# Main_Board_-_Double_v3.net
KiCad netlist of a schematic drawn in EAGLE
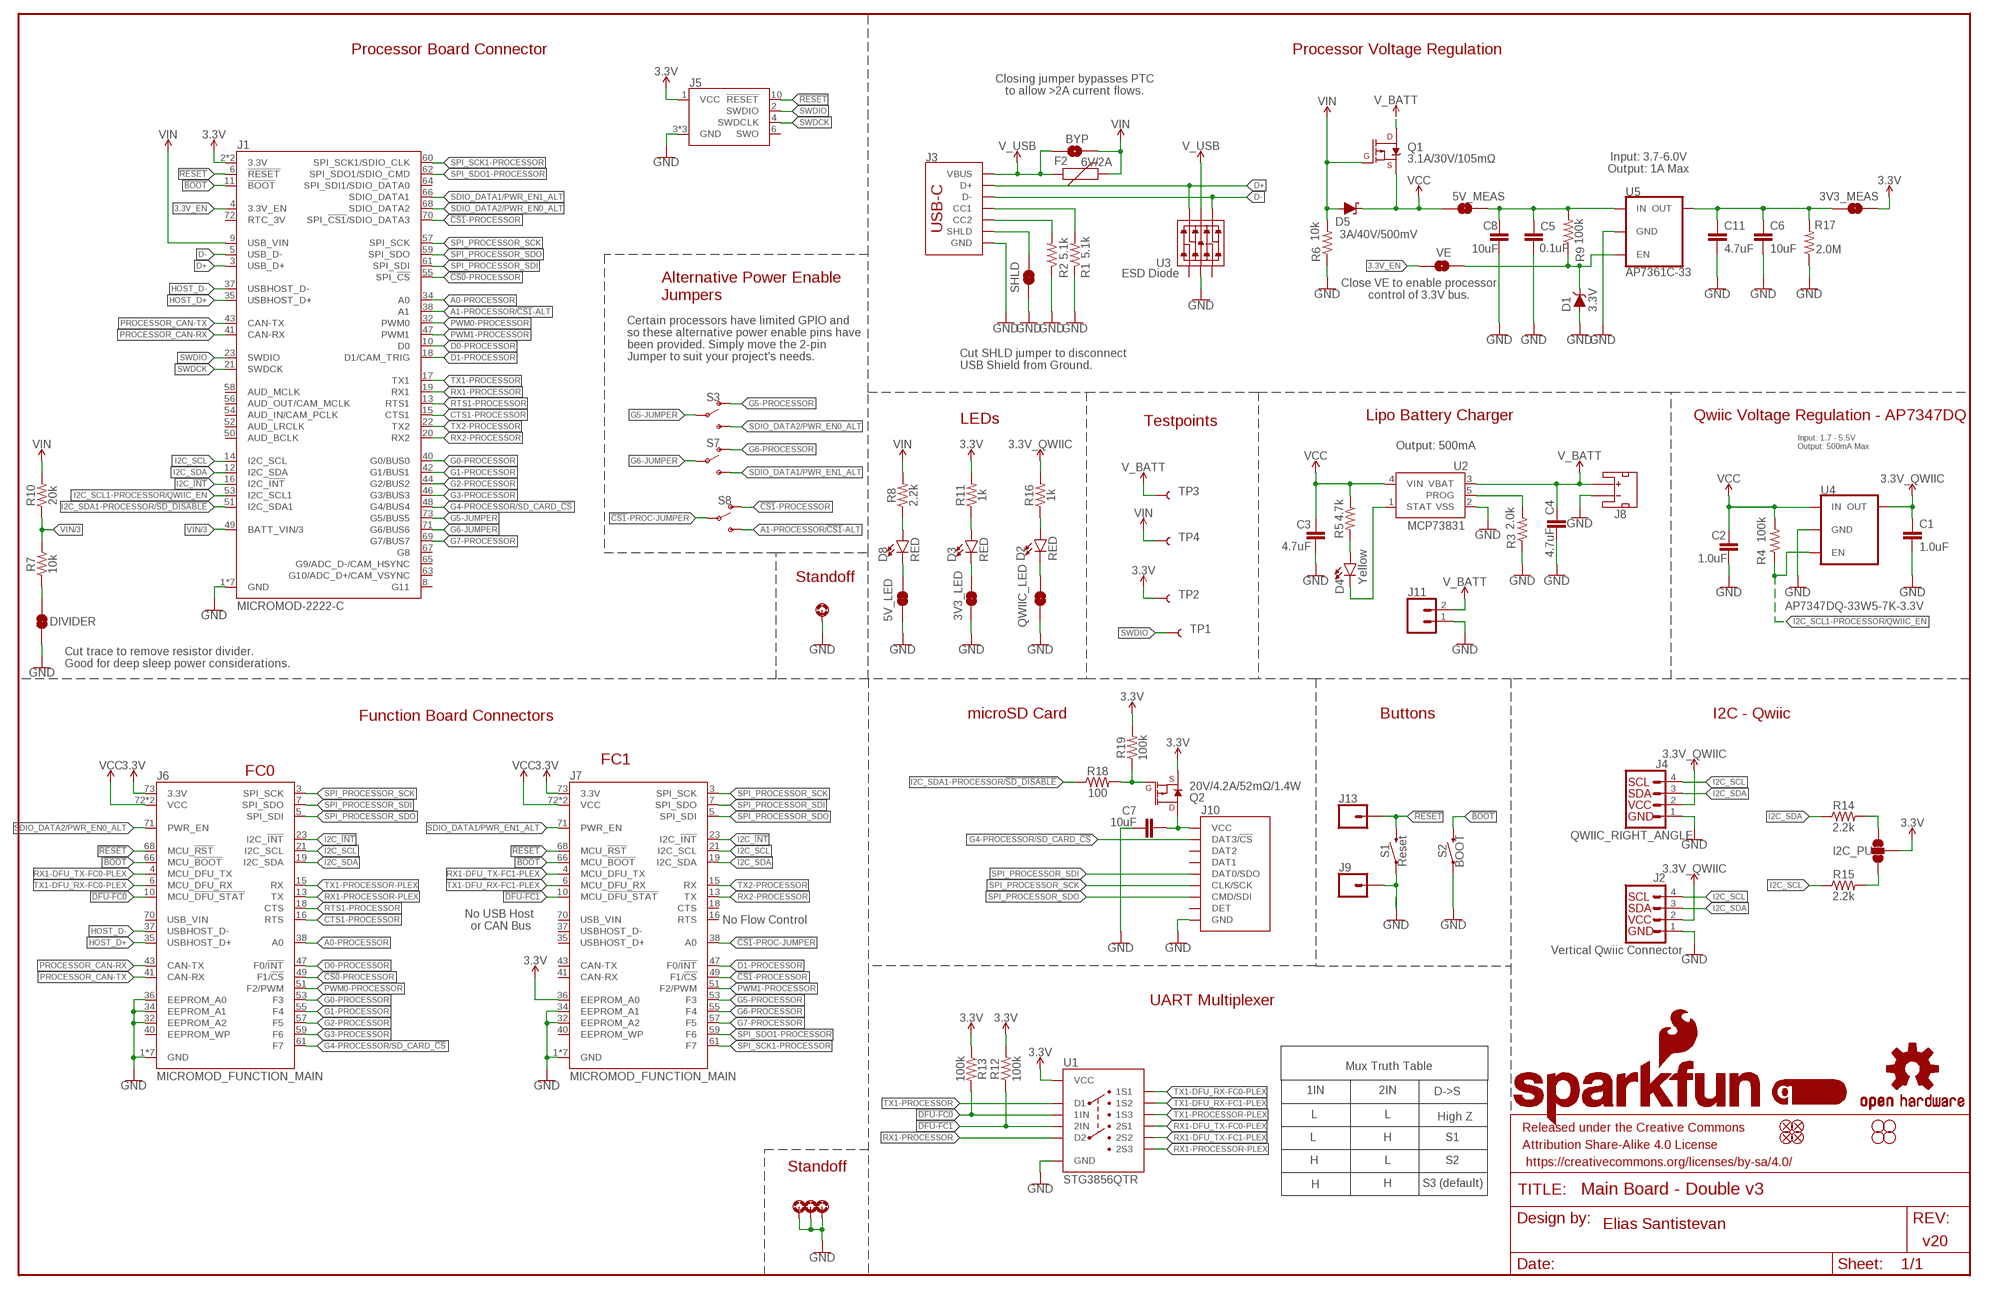
[diagram p0: schematic, sheet 1]

(export (version "E")
  (design (tool "Eeschema 10.0.6"))
  (components
    (comp (ref "3V3_LED")
      (value "JUMPER-SMT_2_NC_TRACE_SILK")
      (footprint "eagle-import:SMT-JUMPER_2_NC_TRACE_SILK")
      (libsource (lib "eagle-import") (part "JUMPER-SMT_2_NC_TRACE_SILK"))
    )
    (comp (ref "3V3_MEAS")
      (value "JUMPER-COMBO_2_NC_TRACE")
      (footprint "eagle-import:COMBO-JUMPER_2_NC_TRACE")
      (libsource (lib "eagle-import") (part "JUMPER-COMBO_2_NC_TRACE"))
    )
    (comp (ref "5V_LED")
      (value "JUMPER-SMT_2_NC_TRACE_SILK")
      (footprint "eagle-import:SMT-JUMPER_2_NC_TRACE_SILK")
      (libsource (lib "eagle-import") (part "JUMPER-SMT_2_NC_TRACE_SILK"))
    )
    (comp (ref "5V_MEAS")
      (value "JUMPER-COMBO_2_NC_TRACE")
      (footprint "eagle-import:COMBO-JUMPER_2_NC_TRACE")
      (libsource (lib "eagle-import") (part "JUMPER-COMBO_2_NC_TRACE"))
    )
    (comp (ref "BYP")
      (value "JUMPER-SMT_2_NO_SILK")
      (footprint "eagle-import:SMT-JUMPER_2_NO_SILK")
      (libsource (lib "eagle-import") (part "JUMPER-SMT_2_NO_SILK"))
    )
    (comp (ref "C1")
      (value "1.0uF")
      (footprint "eagle-import:0603")
      (libsource (lib "eagle-import") (part "1.0UF-0603-16V-10%"))
    )
    (comp (ref "C2")
      (value "1.0uF")
      (footprint "eagle-import:0603")
      (libsource (lib "eagle-import") (part "1.0UF-0603-16V-10%"))
    )
    (comp (ref "C3")
      (value "4.7uF")
      (footprint "eagle-import:0603")
      (libsource (lib "eagle-import") (part "4.7UF-0603-6.3V-(10%)"))
    )
    (comp (ref "C4")
      (value "4.7uF")
      (footprint "eagle-import:0603")
      (libsource (lib "eagle-import") (part "4.7UF-0603-35V-(20%)"))
    )
    (comp (ref "C5")
      (value "0.1uF")
      (footprint "eagle-import:0603")
      (libsource (lib "eagle-import") (part "0.1UF-0603-25V-(+80/-20%)"))
    )
    (comp (ref "C6")
      (value "10uF")
      (footprint "eagle-import:0805")
      (libsource (lib "eagle-import") (part "10UF-0805-10V-10%"))
    )
    (comp (ref "C7")
      (value "10uF")
      (footprint "eagle-import:0603")
      (libsource (lib "eagle-import") (part "10UF-0603-6.3V-20%"))
    )
    (comp (ref "C8")
      (value "10uF")
      (footprint "eagle-import:0805")
      (libsource (lib "eagle-import") (part "10UF-0805-10V-10%"))
    )
    (comp (ref "C11")
      (value "4.7uF")
      (footprint "eagle-import:0603")
      (libsource (lib "eagle-import") (part "4.7UF-0603-6.3V-(10%)"))
    )
    (comp (ref "D1")
      (value "3.3V")
      (footprint "eagle-import:SOD-323")
      (libsource (lib "eagle-import") (part "DIODE-ZENER-MM3Z3V3T1G"))
    )
    (comp (ref "D2")
      (value "RED")
      (footprint "eagle-import:LED-0603")
      (libsource (lib "eagle-import") (part "LED-RED0603"))
    )
    (comp (ref "D3")
      (value "RED")
      (footprint "eagle-import:LED-0603")
      (libsource (lib "eagle-import") (part "LED-RED0603"))
    )
    (comp (ref "D4")
      (value "Yellow")
      (footprint "eagle-import:LED-0603")
      (libsource (lib "eagle-import") (part "LED-YELLOW0603"))
    )
    (comp (ref "D5")
      (value "3A/40V/500mV")
      (footprint "eagle-import:SMA-DIODE")
      (libsource (lib "eagle-import") (part "DIODE-SCHOTTKY-B340A"))
    )
    (comp (ref "D8")
      (value "RED")
      (footprint "eagle-import:LED-0603")
      (libsource (lib "eagle-import") (part "LED-RED0603"))
    )
    (comp (ref "DIVIDER")
      (value "JUMPER-SMT_2_NC_TRACE_SILK")
      (footprint "eagle-import:SMT-JUMPER_2_NC_TRACE_SILK")
      (libsource (lib "eagle-import") (part "JUMPER-SMT_2_NC_TRACE_SILK"))
    )
    (comp (ref "F2")
      (value "6V/2A")
      (footprint "eagle-import:1210")
      (libsource (lib "eagle-import") (part "PPTC_6V2A"))
    )
    (comp (ref "FD1")
      (value "FIDUCIAL1X2")
      (footprint "eagle-import:FIDUCIAL-1X2")
      (libsource (lib "eagle-import") (part "FIDUCIAL1X2"))
    )
    (comp (ref "FD2")
      (value "FIDUCIAL1X2")
      (footprint "eagle-import:FIDUCIAL-1X2")
      (libsource (lib "eagle-import") (part "FIDUCIAL1X2"))
    )
    (comp (ref "FD3")
      (value "FIDUCIAL1X2")
      (footprint "eagle-import:FIDUCIAL-1X2")
      (libsource (lib "eagle-import") (part "FIDUCIAL1X2"))
    )
    (comp (ref "FD4")
      (value "FIDUCIAL1X2")
      (footprint "eagle-import:FIDUCIAL-1X2")
      (libsource (lib "eagle-import") (part "FIDUCIAL1X2"))
    )
    (comp (ref "FRAME1")
      (value "FRAME-LEDGER")
      (footprint "eagle-import:CREATIVE_COMMONS")
      (libsource (lib "eagle-import") (part "FRAME-LEDGER"))
    )
    (comp (ref "H2")
      (value "STAND-OFF-REFLOW-M2.5_2.5MM_TALL")
      (footprint "eagle-import:STAND-OFF-REFLOW-M2.5")
      (libsource (lib "eagle-import") (part "STAND-OFF-REFLOW-M2.5_2.5MM_TALL"))
    )
    (comp (ref "H3")
      (value "STAND-OFF-REFLOW-M2.5_2.5MM_TALL")
      (footprint "eagle-import:STAND-OFF-REFLOW-M2.5")
      (libsource (lib "eagle-import") (part "STAND-OFF-REFLOW-M2.5_2.5MM_TALL"))
    )
    (comp (ref "H4")
      (value "STAND-OFF-REFLOW-M2.5_2.5MM_TALL")
      (footprint "eagle-import:STAND-OFF-REFLOW-M2.5")
      (libsource (lib "eagle-import") (part "STAND-OFF-REFLOW-M2.5_2.5MM_TALL"))
    )
    (comp (ref "H8")
      (value "STAND-OFF-REFLOW-M2.5_2.5MM_TALL")
      (footprint "eagle-import:STAND-OFF-REFLOW-M2.5")
      (libsource (lib "eagle-import") (part "STAND-OFF-REFLOW-M2.5_2.5MM_TALL"))
    )
    (comp (ref "H14")
      (value "STAND-OFFTIGHT")
      (footprint "eagle-import:STAND-OFF-TIGHT")
      (libsource (lib "eagle-import") (part "STAND-OFFTIGHT"))
    )
    (comp (ref "H15")
      (value "STAND-OFFTIGHT")
      (footprint "eagle-import:STAND-OFF-TIGHT")
      (libsource (lib "eagle-import") (part "STAND-OFFTIGHT"))
    )
    (comp (ref "H16")
      (value "STAND-OFFTIGHT")
      (footprint "eagle-import:STAND-OFF-TIGHT")
      (libsource (lib "eagle-import") (part "STAND-OFFTIGHT"))
    )
    (comp (ref "H17")
      (value "STAND-OFFTIGHT")
      (footprint "eagle-import:STAND-OFF-TIGHT")
      (libsource (lib "eagle-import") (part "STAND-OFFTIGHT"))
    )
    (comp (ref "I2C_PU")
      (value "JUMPER-SMT_3_2-NC_TRACE_SILK")
      (footprint "eagle-import:SMT-JUMPER_3_2-NC_TRACE_SILK")
      (libsource (lib "eagle-import") (part "JUMPER-SMT_3_2-NC_TRACE_SILK"))
    )
    (comp (ref "J1")
      (value "MICROMOD-2222-C")
      (footprint "eagle-import:M.2-CONNECTOR-E")
      (libsource (lib "eagle-import") (part "MICROMOD-2222-C"))
    )
    (comp (ref "J2")
      (value "Vertical Qwiic Connector")
      (footprint "eagle-import:JST04_1MM_VERT")
      (libsource (lib "eagle-import") (part "QWIIC_CONNECTOR"))
    )
    (comp (ref "J3")
      (value "USB_C_2-LAYER_PADS")
      (footprint "eagle-import:USB-C-16P-2LAYER-PADS")
      (libsource (lib "eagle-import") (part "USB_C_2-LAYER_PADS"))
    )
    (comp (ref "J4")
      (value "QWIIC_RIGHT_ANGLE")
      (footprint "eagle-import:JST04_1MM_RA")
      (libsource (lib "eagle-import") (part "QWIIC_CONNECTORJS-1MM"))
    )
    (comp (ref "J5")
      (value "CORTEX_JTAG_DEBUG_MINIMUM_PTH")
      (footprint "eagle-import:2X5-PTH-1.27MM")
      (libsource (lib "eagle-import") (part "CORTEX_JTAG_DEBUG_MINIMUM_PTH"))
    )
    (comp (ref "J6")
      (value "MICROMOD_FUNCTION_MAIN")
      (footprint "eagle-import:M.2-CONNECTOR-E-FUNCTION-STANDARD")
      (libsource (lib "eagle-import") (part "MICROMOD_FUNCTION_MAIN"))
    )
    (comp (ref "J7")
      (value "MICROMOD_FUNCTION_MAIN")
      (footprint "eagle-import:M.2-CONNECTOR-E-FUNCTION-STANDARD")
      (libsource (lib "eagle-import") (part "MICROMOD_FUNCTION_MAIN"))
    )
    (comp (ref "J8")
      (value "JST_2MM_MALE")
      (footprint "eagle-import:JST-2-SMD")
      (libsource (lib "eagle-import") (part "JST_2MM_MALE"))
    )
    (comp (ref "J9")
      (value "CONN_01PTH_NO_SILK_YES_STOP")
      (footprint "eagle-import:1X01_NO_SILK")
      (libsource (lib "eagle-import") (part "CONN_01PTH_NO_SILK_YES_STOP"))
    )
    (comp (ref "J10")
      (value "MICRO-SD-PUSH-PUSH-EXT-PIN")
      (footprint "eagle-import:MICROSD-EXTERNALPIN")
      (libsource (lib "eagle-import") (part "MICRO-SD-PUSH-PUSH-EXT-PIN"))
    )
    (comp (ref "J11")
      (value "CONN_021X02_NO_SILK")
      (footprint "eagle-import:1X02_NO_SILK")
      (libsource (lib "eagle-import") (part "CONN_021X02_NO_SILK"))
    )
    (comp (ref "J13")
      (value "CONN_01PTH_NO_SILK_YES_STOP")
      (footprint "eagle-import:1X01_NO_SILK")
      (libsource (lib "eagle-import") (part "CONN_01PTH_NO_SILK_YES_STOP"))
    )
    (comp (ref "LOGO1")
      (value "QWIIC_LOGO_8MM")
      (footprint "eagle-import:QWIIC_8MM")
      (libsource (lib "eagle-import") (part "QWIIC_LOGO_8MM"))
    )
    (comp (ref "LOGO2")
      (value "SFE_LOGO_NAME_FLAME.3_INCH")
      (footprint "eagle-import:SFE_LOGO_NAME_FLAME_.3")
      (libsource (lib "eagle-import") (part "SFE_LOGO_NAME_FLAME.3_INCH"))
    )
    (comp (ref "LOGO3")
      (value "OSHW-LOGOL")
      (footprint "eagle-import:OSHW-LOGO-L")
      (libsource (lib "eagle-import") (part "OSHW-LOGOL"))
    )
    (comp (ref "Q1")
      (value "3.1A/30V/105mΩ")
      (footprint "eagle-import:SOT23-3")
      (libsource (lib "eagle-import") (part "MOSFET_PCH-DMG2307L"))
    )
    (comp (ref "Q2")
      (value "20V/4.2A/52mΩ/1.4W")
      (footprint "eagle-import:SOT23-3")
      (libsource (lib "eagle-import") (part "MOSFET_PCH-DMG2305UX-7"))
    )
    (comp (ref "QWIIC_LED")
      (value "JUMPER-SMT_2_NC_TRACE_SILK")
      (footprint "eagle-import:SMT-JUMPER_2_NC_TRACE_SILK")
      (libsource (lib "eagle-import") (part "JUMPER-SMT_2_NC_TRACE_SILK"))
    )
    (comp (ref "R1")
      (value "5.1k")
      (footprint "eagle-import:0603")
      (libsource (lib "eagle-import") (part "5.1KOHM5.1KOHM-0603-1/10W-1%"))
    )
    (comp (ref "R2")
      (value "5.1k")
      (footprint "eagle-import:0603")
      (libsource (lib "eagle-import") (part "5.1KOHM5.1KOHM-0603-1/10W-1%"))
    )
    (comp (ref "R3")
      (value "2.0k")
      (footprint "eagle-import:0603")
      (libsource (lib "eagle-import") (part "2.0KOHM-0603-1/10W-5%"))
    )
    (comp (ref "R4")
      (value "100k")
      (footprint "eagle-import:0603")
      (libsource (lib "eagle-import") (part "100KOHM-0603-1/10W-1%"))
    )
    (comp (ref "R5")
      (value "4.7k")
      (footprint "eagle-import:0603")
      (libsource (lib "eagle-import") (part "4.7KOHM-0603-1/10W-1%"))
    )
    (comp (ref "R6")
      (value "10k")
      (footprint "eagle-import:0603")
      (libsource (lib "eagle-import") (part "10KOHM-0603-1/10W-1%"))
    )
    (comp (ref "R7")
      (value "10k")
      (footprint "eagle-import:0603")
      (libsource (lib "eagle-import") (part "10KOHM-0603-1/10W-1%"))
    )
    (comp (ref "R8")
      (value "2.2k")
      (footprint "eagle-import:0603")
      (libsource (lib "eagle-import") (part "2.2KOHM-0603-1/10W-1%"))
    )
    (comp (ref "R9")
      (value "100k")
      (footprint "eagle-import:0603")
      (libsource (lib "eagle-import") (part "100KOHM-0603-1/10W-1%"))
    )
    (comp (ref "R10")
      (value "20k")
      (footprint "eagle-import:0603")
      (libsource (lib "eagle-import") (part "20KOHM-0603-1/10W-1%"))
    )
    (comp (ref "R11")
      (value "1k")
      (footprint "eagle-import:0603")
      (libsource (lib "eagle-import") (part "1KOHM-0603-1/10W-1%"))
    )
    (comp (ref "R12")
      (value "100k")
      (footprint "eagle-import:0603")
      (libsource (lib "eagle-import") (part "100KOHM-0603-1/10W-1%"))
    )
    (comp (ref "R13")
      (value "100k")
      (footprint "eagle-import:0603")
      (libsource (lib "eagle-import") (part "100KOHM-0603-1/10W-1%"))
    )
    (comp (ref "R14")
      (value "2.2k")
      (footprint "eagle-import:0603")
      (libsource (lib "eagle-import") (part "2.2KOHM-0603-1/10W-1%"))
    )
    (comp (ref "R15")
      (value "2.2k")
      (footprint "eagle-import:0603")
      (libsource (lib "eagle-import") (part "2.2KOHM-0603-1/10W-1%"))
    )
    (comp (ref "R16")
      (value "1k")
      (footprint "eagle-import:0603")
      (libsource (lib "eagle-import") (part "1KOHM-0603-1/10W-1%"))
    )
    (comp (ref "R17")
      (value "2.0M")
      (footprint "eagle-import:0603")
      (libsource (lib "eagle-import") (part "2MOHMS-0603-1/10W-1%"))
    )
    (comp (ref "R18")
      (value "100")
      (footprint "eagle-import:0603")
      (libsource (lib "eagle-import") (part "100OHM-0603-1/10W-1%"))
    )
    (comp (ref "R19")
      (value "100k")
      (footprint "eagle-import:0603")
      (libsource (lib "eagle-import") (part "100KOHM-0603-1/10W-1%"))
    )
    (comp (ref "S1")
      (value "Reset")
      (footprint "eagle-import:TACTILE_SWITCH_SMD_5.2MM")
      (libsource (lib "eagle-import") (part "MOMENTARY-SWITCH-SPST-SMD-5.2-TALL-REDUNDANT"))
    )
    (comp (ref "S2")
      (value "BOOT")
      (footprint "eagle-import:TACTILE_SWITCH_SMD_5.2MM")
      (libsource (lib "eagle-import") (part "MOMENTARY-SWITCH-SPST-SMD-5.2-TALL-REDUNDANT"))
    )
    (comp (ref "S3")
      (value "SWITCH-SPDT-SMD-RIGHT-ANGLE")
      (footprint "eagle-import:SWITCH_SPST_SMD_A")
      (libsource (lib "eagle-import") (part "SWITCH-SPDT-SMD-RIGHT-ANGLE"))
    )
    (comp (ref "S7")
      (value "SWITCH-SPDT-SMD-RIGHT-ANGLE")
      (footprint "eagle-import:SWITCH_SPST_SMD_A")
      (libsource (lib "eagle-import") (part "SWITCH-SPDT-SMD-RIGHT-ANGLE"))
    )
    (comp (ref "S8")
      (value "SWITCH-SPDT-SMD-RIGHT-ANGLE")
      (footprint "eagle-import:SWITCH_SPST_SMD_A")
      (libsource (lib "eagle-import") (part "SWITCH-SPDT-SMD-RIGHT-ANGLE"))
    )
    (comp (ref "SHLD")
      (value "JUMPER-SMT_2_NC_TRACE_SILK")
      (footprint "eagle-import:SMT-JUMPER_2_NC_TRACE_SILK")
      (libsource (lib "eagle-import") (part "JUMPER-SMT_2_NC_TRACE_SILK"))
    )
    (comp (ref "TP1")
      (value "TEST-POINT3X5")
      (footprint "eagle-import:PAD.03X.05")
      (libsource (lib "eagle-import") (part "TEST-POINT3X5"))
    )
    (comp (ref "TP2")
      (value "TEST-POINT3X5")
      (footprint "eagle-import:PAD.03X.05")
      (libsource (lib "eagle-import") (part "TEST-POINT3X5"))
    )
    (comp (ref "TP3")
      (value "TEST-POINT3X5")
      (footprint "eagle-import:PAD.03X.05")
      (libsource (lib "eagle-import") (part "TEST-POINT3X5"))
    )
    (comp (ref "TP4")
      (value "TEST-POINT3X5")
      (footprint "eagle-import:PAD.03X.05")
      (libsource (lib "eagle-import") (part "TEST-POINT3X5"))
    )
    (comp (ref "U1")
      (value "STG3856QTR")
      (footprint "eagle-import:STG3856")
      (libsource (lib "eagle-import") (part "STG3856QTR"))
    )
    (comp (ref "U2")
      (value "MCP73831")
      (footprint "eagle-import:SOT23-5")
      (libsource (lib "eagle-import") (part "MCP73831"))
    )
    (comp (ref "U3")
      (value "ESD Diode")
      (footprint "eagle-import:SOT-23-6")
      (libsource (lib "eagle-import") (part "TVS_DIODE_ARRAYSMD"))
    )
    (comp (ref "U4")
      (value "AP7347DQ-33W5-7K-3.3V")
      (footprint "eagle-import:SOT25")
      (libsource (lib "eagle-import") (part "AP7347DQ-33W5-7K-3.3V"))
    )
    (comp (ref "U5")
      (value "AP7361C-33")
      (footprint "eagle-import:UDFN-8")
      (libsource (lib "eagle-import") (part "AP7361C-33FGEUDFN-8"))
    )
    (comp (ref "VE")
      (value "JUMPER-SMT_2_NO_SILK")
      (footprint "eagle-import:SMT-JUMPER_2_NO_SILK")
      (libsource (lib "eagle-import") (part "JUMPER-SMT_2_NO_SILK"))
    )
  )
  (nets
    (net (code "1") (name "/A1-PROCESSOR{slash}~{CS1}-ALT") (class "Default")
      (node (ref "J1") (pin "38") (pinfunction "A1_38") (pintype "bidirectional"))
      (node (ref "S8") (pin "3") (pinfunction "S_3") (pintype "passive"))
    )
    (net (code "2") (name "/G4-PROCESSOR{slash}SD_CARD_~{CS}") (class "Default")
      (node (ref "J1") (pin "48") (pinfunction "G4/BUS4_48") (pintype "bidirectional"))
      (node (ref "J10") (pin "2") (pinfunction "DAT3/~{CS}_2") (pintype "bidirectional"))
      (node (ref "J6") (pin "61") (pinfunction "F7_61") (pintype "bidirectional"))
    )
    (net (code "3") (name "/I2C_SDA1-PROCESSOR{slash}~{SD_DISABLE}") (class "Default")
      (node (ref "J1") (pin "51") (pinfunction "I2C_SDA1_51") (pintype "bidirectional"))
      (node (ref "R18") (pin "1") (pinfunction "1_1") (pintype "passive"))
    )
    (net (code "4") (name "/I2C_~{INT}") (class "Default")
      (node (ref "J1") (pin "16") (pinfunction "I2C_~{INT}_16") (pintype "bidirectional"))
      (node (ref "J6") (pin "23") (pinfunction "I2C_~{INT}_23") (pintype "bidirectional"))
      (node (ref "J7") (pin "23") (pinfunction "I2C_~{INT}_23") (pintype "bidirectional"))
    )
    (net (code "5") (name "/~{BOOT}") (class "Default")
      (node (ref "J1") (pin "11") (pinfunction "~{BOOT}_11") (pintype "bidirectional"))
      (node (ref "J6") (pin "66") (pinfunction "MCU_~{BOOT}_66") (pintype "bidirectional"))
      (node (ref "J7") (pin "66") (pinfunction "MCU_~{BOOT}_66") (pintype "bidirectional"))
      (node (ref "S2") (pin "3") (pinfunction "2_3") (pintype "passive"))
      (node (ref "S2") (pin "4") (pinfunction "2_4") (pintype "passive"))
    )
    (net (code "6") (name "/~{CS0}-PROCESSOR") (class "Default")
      (node (ref "J1") (pin "55") (pinfunction "SPI_~{CS}_55") (pintype "bidirectional"))
      (node (ref "J6") (pin "49") (pinfunction "F1/~{CS}_49") (pintype "bidirectional"))
    )
    (net (code "7") (name "/~{CS1}-PROC-JUMPER") (class "Default")
      (node (ref "J7") (pin "38") (pinfunction "A0_38") (pintype "bidirectional"))
      (node (ref "S8") (pin "2") (pinfunction "P_2") (pintype "passive"))
    )
    (net (code "8") (name "/~{CS1}-PROCESSOR") (class "Default")
      (node (ref "J1") (pin "70") (pinfunction "SPI_~{CS1}/SDIO_DATA3_70") (pintype "bidirectional"))
      (node (ref "J7") (pin "49") (pinfunction "F1/~{CS}_49") (pintype "bidirectional"))
      (node (ref "S8") (pin "1") (pinfunction "O_1") (pintype "passive"))
    )
    (net (code "9") (name "/~{DFU-FC0}") (class "Default")
      (node (ref "J6") (pin "10") (pinfunction "MCU_~{DFU_STAT}_10") (pintype "bidirectional"))
      (node (ref "R13") (pin "2") (pinfunction "2_2") (pintype "passive"))
      (node (ref "U1") (pin "P12") (pinfunction "1IN_P12") (pintype "bidirectional"))
    )
    (net (code "10") (name "/~{DFU-FC1}") (class "Default")
      (node (ref "J7") (pin "10") (pinfunction "MCU_~{DFU_STAT}_10") (pintype "bidirectional"))
      (node (ref "R12") (pin "1") (pinfunction "1_1") (pintype "passive"))
      (node (ref "U1") (pin "P10") (pinfunction "2IN_P10") (pintype "bidirectional"))
    )
    (net (code "11") (name "/~{RESET}") (class "Default")
      (node (ref "J1") (pin "6") (pinfunction "~{RESET}_6") (pintype "bidirectional"))
      (node (ref "J13") (pin "1") (pinfunction "1_1") (pintype "passive"))
      (node (ref "J5") (pin "10") (pinfunction "~{RESET}_10") (pintype "bidirectional"))
      (node (ref "J6") (pin "68") (pinfunction "MCU_~{RST}_68") (pintype "bidirectional"))
      (node (ref "J7") (pin "68") (pinfunction "MCU_~{RST}_68") (pintype "bidirectional"))
      (node (ref "S1") (pin "3") (pinfunction "2_3") (pintype "passive"))
      (node (ref "S1") (pin "4") (pinfunction "2_4") (pintype "passive"))
    )
    (net (code "12") (name "3.3V") (class "Default")
      (node (ref "3V3_MEAS") (pin "2") (pinfunction "2_2") (pintype "passive"))
      (node (ref "3V3_MEAS") (pin "4") (pinfunction "2_4") (pintype "passive"))
      (node (ref "I2C_PU") (pin "2") (pinfunction "2_2") (pintype "passive"))
      (node (ref "J1") (pin "2") (pinfunction "3.3V_2") (pintype "bidirectional"))
      (node (ref "J1") (pin "74") (pinfunction "3.3V_74") (pintype "bidirectional"))
      (node (ref "J5") (pin "1") (pinfunction "VCC_1") (pintype "bidirectional"))
      (node (ref "J6") (pin "73") (pinfunction "3.3V_73") (pintype "bidirectional"))
      (node (ref "J7") (pin "36") (pinfunction "EEPROM_A0_36") (pintype "bidirectional"))
      (node (ref "J7") (pin "73") (pinfunction "3.3V_73") (pintype "bidirectional"))
      (node (ref "Q2") (pin "2") (pinfunction "S_2") (pintype "bidirectional"))
      (node (ref "R11") (pin "2") (pinfunction "2_2") (pintype "passive"))
      (node (ref "R12") (pin "2") (pinfunction "2_2") (pintype "passive"))
      (node (ref "R13") (pin "1") (pinfunction "1_1") (pintype "passive"))
      (node (ref "R19") (pin "2") (pinfunction "2_2") (pintype "passive"))
      (node (ref "TP2") (pin "1") (pinfunction "1_1") (pintype "bidirectional"))
      (node (ref "U1") (pin "P11") (pinfunction "VCC_P11") (pintype "power_in"))
    )
    (net (code "13") (name "3.3V_EN") (class "Default")
      (node (ref "J1") (pin "4") (pinfunction "3.3V_EN_4") (pintype "bidirectional"))
      (node (ref "VE") (pin "1") (pinfunction "1_1") (pintype "passive"))
    )
    (net (code "14") (name "3.3V_QWIIC") (class "Default")
      (node (ref "C1") (pin "1") (pinfunction "1_1") (pintype "passive"))
      (node (ref "J2") (pin "2") (pinfunction "2_2") (pintype "power_in"))
      (node (ref "J4") (pin "2") (pinfunction "2_2") (pintype "power_in"))
      (node (ref "R16") (pin "2") (pinfunction "2_2") (pintype "passive"))
      (node (ref "U4") (pin "5") (pinfunction "OUT_5") (pintype "passive"))
    )
    (net (code "15") (name "A0-PROCESSOR") (class "Default")
      (node (ref "J1") (pin "34") (pinfunction "A0_34") (pintype "bidirectional"))
      (node (ref "J6") (pin "38") (pinfunction "A0_38") (pintype "bidirectional"))
    )
    (net (code "16") (name "CTS1-PROCESSOR") (class "Default")
      (node (ref "J1") (pin "15") (pinfunction "CTS1_15") (pintype "bidirectional"))
      (node (ref "J6") (pin "16") (pinfunction "RTS_16") (pintype "bidirectional"))
    )
    (net (code "17") (name "D+") (class "Default")
      (node (ref "J1") (pin "3") (pinfunction "USB_D+_3") (pintype "bidirectional"))
      (node (ref "J3") (pin "A6") (pinfunction "D+_A6") (pintype "bidirectional"))
      (node (ref "J3") (pin "B6") (pinfunction "D+_B6") (pintype "bidirectional"))
      (node (ref "U3") (pin "6") (pinfunction "IO4_6") (pintype "bidirectional"))
    )
    (net (code "18") (name "D-") (class "Default")
      (node (ref "J1") (pin "5") (pinfunction "USB_D-_5") (pintype "bidirectional"))
      (node (ref "J3") (pin "A7") (pinfunction "D-_A7") (pintype "bidirectional"))
      (node (ref "J3") (pin "B7") (pinfunction "D-_B7") (pintype "bidirectional"))
      (node (ref "U3") (pin "4") (pinfunction "IO3_4") (pintype "bidirectional"))
    )
    (net (code "19") (name "D0-PROCESSOR") (class "Default")
      (node (ref "J1") (pin "10") (pinfunction "D0_10") (pintype "bidirectional"))
      (node (ref "J6") (pin "47") (pinfunction "F0/~{INT}_47") (pintype "bidirectional"))
    )
    (net (code "20") (name "D1-PROCESSOR") (class "Default")
      (node (ref "J1") (pin "18") (pinfunction "D1/CAM_TRIG_18") (pintype "bidirectional"))
      (node (ref "J7") (pin "47") (pinfunction "F0/~{INT}_47") (pintype "bidirectional"))
    )
    (net (code "21") (name "G0-PROCESSOR") (class "Default")
      (node (ref "J1") (pin "40") (pinfunction "G0/BUS0_40") (pintype "bidirectional"))
      (node (ref "J6") (pin "53") (pinfunction "F3_53") (pintype "bidirectional"))
    )
    (net (code "22") (name "G1-PROCESSOR") (class "Default")
      (node (ref "J1") (pin "42") (pinfunction "G1/BUS1_42") (pintype "bidirectional"))
      (node (ref "J6") (pin "55") (pinfunction "F4_55") (pintype "bidirectional"))
    )
    (net (code "23") (name "G2-PROCESSOR") (class "Default")
      (node (ref "J1") (pin "44") (pinfunction "G2/BUS2_44") (pintype "bidirectional"))
      (node (ref "J6") (pin "57") (pinfunction "F5_57") (pintype "bidirectional"))
    )
    (net (code "24") (name "G3-PROCESSOR") (class "Default")
      (node (ref "J1") (pin "46") (pinfunction "G3/BUS3_46") (pintype "bidirectional"))
      (node (ref "J6") (pin "59") (pinfunction "F6_59") (pintype "bidirectional"))
    )
    (net (code "25") (name "G5-JUMPER") (class "Default")
      (node (ref "J1") (pin "73") (pinfunction "G5/BUS5_73") (pintype "bidirectional"))
      (node (ref "S3") (pin "2") (pinfunction "P_2") (pintype "passive"))
    )
    (net (code "26") (name "G5-PROCESSOR") (class "Default")
      (node (ref "J7") (pin "53") (pinfunction "F3_53") (pintype "bidirectional"))
      (node (ref "S3") (pin "1") (pinfunction "O_1") (pintype "passive"))
    )
    (net (code "27") (name "G6-JUMPER") (class "Default")
      (node (ref "J1") (pin "71") (pinfunction "G6/BUS6_71") (pintype "bidirectional"))
      (node (ref "S7") (pin "2") (pinfunction "P_2") (pintype "passive"))
    )
    (net (code "28") (name "G6-PROCESSOR") (class "Default")
      (node (ref "J7") (pin "55") (pinfunction "F4_55") (pintype "bidirectional"))
      (node (ref "S7") (pin "1") (pinfunction "O_1") (pintype "passive"))
    )
    (net (code "29") (name "G7-PROCESSOR") (class "Default")
      (node (ref "J1") (pin "69") (pinfunction "G7/BUS7_69") (pintype "bidirectional"))
      (node (ref "J7") (pin "57") (pinfunction "F5_57") (pintype "bidirectional"))
    )
    (net (code "30") (name "GND") (class "Default")
      (node (ref "3V3_LED") (pin "1") (pinfunction "1_1") (pintype "passive"))
      (node (ref "5V_LED") (pin "1") (pinfunction "1_1") (pintype "passive"))
      (node (ref "C1") (pin "2") (pinfunction "2_2") (pintype "passive"))
      (node (ref "C11") (pin "2") (pinfunction "2_2") (pintype "passive"))
      (node (ref "C2") (pin "2") (pinfunction "2_2") (pintype "passive"))
      (node (ref "C3") (pin "2") (pinfunction "2_2") (pintype "passive"))
      (node (ref "C4") (pin "2") (pinfunction "2_2") (pintype "passive"))
      (node (ref "C5") (pin "2") (pinfunction "2_2") (pintype "passive"))
      (node (ref "C6") (pin "2") (pinfunction "2_2") (pintype "passive"))
      (node (ref "C7") (pin "1") (pinfunction "1_1") (pintype "passive"))
      (node (ref "C8") (pin "2") (pinfunction "2_2") (pintype "passive"))
      (node (ref "D1") (pin "A") (pinfunction "A_A") (pintype "passive"))
      (node (ref "DIVIDER") (pin "1") (pinfunction "1_1") (pintype "passive"))
      (node (ref "H2") (pin "1") (pinfunction "1_1") (pintype "bidirectional"))
      (node (ref "H3") (pin "1") (pinfunction "1_1") (pintype "bidirectional"))
      (node (ref "H4") (pin "1") (pinfunction "1_1") (pintype "bidirectional"))
      (node (ref "H8") (pin "1") (pinfunction "1_1") (pintype "bidirectional"))
      (node (ref "J1") (pin "1") (pinfunction "GND_1") (pintype "bidirectional"))
      (node (ref "J1") (pin "33") (pinfunction "GND_33") (pintype "bidirectional"))
      (node (ref "J1") (pin "36") (pinfunction "GND_36") (pintype "bidirectional"))
      (node (ref "J1") (pin "39") (pinfunction "GND_39") (pintype "bidirectional"))
      (node (ref "J1") (pin "45") (pinfunction "GND_45") (pintype "bidirectional"))
      (node (ref "J1") (pin "7") (pinfunction "GND_7") (pintype "bidirectional"))
      (node (ref "J1") (pin "75") (pinfunction "GND_75") (pintype "bidirectional"))
      (node (ref "J10") (pin "10") (pinfunction "GND_10") (pintype "bidirectional"))
      (node (ref "J10") (pin "11") (pinfunction "GND_11") (pintype "bidirectional"))
      (node (ref "J10") (pin "12") (pinfunction "GND_12") (pintype "bidirectional"))
      (node (ref "J10") (pin "13") (pinfunction "GND_13") (pintype "bidirectional"))
      (node (ref "J10") (pin "6") (pinfunction "GND_6") (pintype "bidirectional"))
      (node (ref "J11") (pin "1") (pinfunction "1_1") (pintype "passive"))
      (node (ref "J2") (pin "1") (pinfunction "1_1") (pintype "power_in"))
      (node (ref "J3") (pin "GND") (pinfunction "GND_GND") (pintype "bidirectional"))
      (node (ref "J3") (pin "GND2") (pinfunction "GND_GND2") (pintype "bidirectional"))
      (node (ref "J4") (pin "1") (pinfunction "1_1") (pintype "power_in"))
      (node (ref "J5") (pin "3") (pinfunction "GND_3") (pintype "bidirectional"))
      (node (ref "J5") (pin "5") (pinfunction "GND_5") (pintype "bidirectional"))
      (node (ref "J5") (pin "9") (pinfunction "GND_9") (pintype "bidirectional"))
      (node (ref "J6") (pin "1") (pinfunction "GND_1") (pintype "bidirectional"))
      (node (ref "J6") (pin "2") (pinfunction "GND_2") (pintype "bidirectional"))
      (node (ref "J6") (pin "32") (pinfunction "EEPROM_A2_32") (pintype "bidirectional"))
      (node (ref "J6") (pin "33") (pinfunction "GND_33") (pintype "bidirectional"))
      (node (ref "J6") (pin "34") (pinfunction "EEPROM_A1_34") (pintype "bidirectional"))
      (node (ref "J6") (pin "36") (pinfunction "EEPROM_A0_36") (pintype "bidirectional"))
      (node (ref "J6") (pin "39") (pinfunction "GND_39") (pintype "bidirectional"))
      (node (ref "J6") (pin "45") (pinfunction "GND_45") (pintype "bidirectional"))
      (node (ref "J6") (pin "75") (pinfunction "GND_75") (pintype "bidirectional"))
      (node (ref "J6") (pin "8") (pinfunction "GND_8") (pintype "bidirectional"))
      (node (ref "J7") (pin "1") (pinfunction "GND_1") (pintype "bidirectional"))
      (node (ref "J7") (pin "2") (pinfunction "GND_2") (pintype "bidirectional"))
      (node (ref "J7") (pin "32") (pinfunction "EEPROM_A2_32") (pintype "bidirectional"))
      (node (ref "J7") (pin "33") (pinfunction "GND_33") (pintype "bidirectional"))
      (node (ref "J7") (pin "34") (pinfunction "EEPROM_A1_34") (pintype "bidirectional"))
      (node (ref "J7") (pin "39") (pinfunction "GND_39") (pintype "bidirectional"))
      (node (ref "J7") (pin "45") (pinfunction "GND_45") (pintype "bidirectional"))
      (node (ref "J7") (pin "75") (pinfunction "GND_75") (pintype "bidirectional"))
      (node (ref "J7") (pin "8") (pinfunction "GND_8") (pintype "bidirectional"))
      (node (ref "J8") (pin "1") (pinfunction "-_1") (pintype "bidirectional"))
      (node (ref "J9") (pin "1") (pinfunction "1_1") (pintype "passive"))
      (node (ref "QWIIC_LED") (pin "1") (pinfunction "1_1") (pintype "passive"))
      (node (ref "R1") (pin "1") (pinfunction "1_1") (pintype "passive"))
      (node (ref "R17") (pin "1") (pinfunction "1_1") (pintype "passive"))
      (node (ref "R2") (pin "1") (pinfunction "1_1") (pintype "passive"))
      (node (ref "R3") (pin "1") (pinfunction "1_1") (pintype "passive"))
      (node (ref "R6") (pin "1") (pinfunction "1_1") (pintype "passive"))
      (node (ref "S1") (pin "1") (pinfunction "1_1") (pintype "passive"))
      (node (ref "S1") (pin "2") (pinfunction "1_2") (pintype "passive"))
      (node (ref "S2") (pin "1") (pinfunction "1_1") (pintype "passive"))
      (node (ref "S2") (pin "2") (pinfunction "1_2") (pintype "passive"))
      (node (ref "SHLD") (pin "1") (pinfunction "1_1") (pintype "passive"))
      (node (ref "U1") (pin "P5") (pinfunction "GND_P5") (pintype "power_in"))
      (node (ref "U2") (pin "2") (pinfunction "VSS_2") (pintype "power_in"))
      (node (ref "U3") (pin "2") (pinfunction "VSS_2") (pintype "bidirectional"))
      (node (ref "U4") (pin "2") (pinfunction "GND_2") (pintype "input"))
      (node (ref "U5") (pin "4") (pinfunction "GND_4") (pintype "input"))
      (node (ref "U5") (pin "EP") (pinfunction "GND_EP") (pintype "input"))
    )
    (net (code "31") (name "HOST_D+") (class "Default")
      (node (ref "J1") (pin "35") (pinfunction "USBHOST_D+_35") (pintype "bidirectional"))
      (node (ref "J6") (pin "35") (pinfunction "USBHOST_D+_35") (pintype "bidirectional"))
    )
    (net (code "32") (name "HOST_D-") (class "Default")
      (node (ref "J1") (pin "37") (pinfunction "USBHOST_D-_37") (pintype "bidirectional"))
      (node (ref "J6") (pin "37") (pinfunction "USBHOST_D-_37") (pintype "bidirectional"))
    )
    (net (code "33") (name "I2C_SCL") (class "Default")
      (node (ref "J1") (pin "14") (pinfunction "I2C_SCL_14") (pintype "bidirectional"))
      (node (ref "J2") (pin "4") (pinfunction "4_4") (pintype "passive"))
      (node (ref "J4") (pin "4") (pinfunction "4_4") (pintype "passive"))
      (node (ref "J6") (pin "21") (pinfunction "I2C_SCL_21") (pintype "bidirectional"))
      (node (ref "J7") (pin "21") (pinfunction "I2C_SCL_21") (pintype "bidirectional"))
      (node (ref "R15") (pin "1") (pinfunction "1_1") (pintype "passive"))
    )
    (net (code "34") (name "I2C_SCL1-PROCESSOR{slash}QWIIC_EN") (class "Default")
      (node (ref "J1") (pin "53") (pinfunction "I2C_SCL1_53") (pintype "bidirectional"))
      (node (ref "R4") (pin "1") (pinfunction "1_1") (pintype "passive"))
      (node (ref "U4") (pin "3") (pinfunction "EN_3") (pintype "input"))
    )
    (net (code "35") (name "I2C_SDA") (class "Default")
      (node (ref "J1") (pin "12") (pinfunction "I2C_SDA_12") (pintype "bidirectional"))
      (node (ref "J2") (pin "3") (pinfunction "3_3") (pintype "passive"))
      (node (ref "J4") (pin "3") (pinfunction "3_3") (pintype "passive"))
      (node (ref "J6") (pin "19") (pinfunction "I2C_SDA_19") (pintype "bidirectional"))
      (node (ref "J7") (pin "19") (pinfunction "I2C_SDA_19") (pintype "bidirectional"))
      (node (ref "R14") (pin "1") (pinfunction "1_1") (pintype "passive"))
    )
    (net (code "36") (name "Net-(3V3_LED-Pad2)") (class "Default")
      (node (ref "3V3_LED") (pin "2") (pinfunction "2_2") (pintype "passive"))
      (node (ref "D3") (pin "C") (pinfunction "C_C") (pintype "passive"))
    )
    (net (code "37") (name "Net-(5V_LED-Pad2)") (class "Default")
      (node (ref "5V_LED") (pin "2") (pinfunction "2_2") (pintype "passive"))
      (node (ref "D8") (pin "C") (pinfunction "C_C") (pintype "passive"))
    )
    (net (code "38") (name "Net-(D2-PadA)") (class "Default")
      (node (ref "D2") (pin "A") (pinfunction "A_A") (pintype "passive"))
      (node (ref "R16") (pin "1") (pinfunction "1_1") (pintype "passive"))
    )
    (net (code "39") (name "Net-(D2-PadC)") (class "Default")
      (node (ref "D2") (pin "C") (pinfunction "C_C") (pintype "passive"))
      (node (ref "QWIIC_LED") (pin "2") (pinfunction "2_2") (pintype "passive"))
    )
    (net (code "40") (name "Net-(D3-PadA)") (class "Default")
      (node (ref "D3") (pin "A") (pinfunction "A_A") (pintype "passive"))
      (node (ref "R11") (pin "1") (pinfunction "1_1") (pintype "passive"))
    )
    (net (code "41") (name "Net-(D4-PadA)") (class "Default")
      (node (ref "D4") (pin "A") (pinfunction "A_A") (pintype "passive"))
      (node (ref "R5") (pin "2") (pinfunction "2_2") (pintype "passive"))
    )
    (net (code "42") (name "Net-(D8-PadA)") (class "Default")
      (node (ref "D8") (pin "A") (pinfunction "A_A") (pintype "passive"))
      (node (ref "R8") (pin "1") (pinfunction "1_1") (pintype "passive"))
    )
    (net (code "43") (name "Net-(DIVIDER-Pad2)") (class "Default")
      (node (ref "DIVIDER") (pin "2") (pinfunction "2_2") (pintype "passive"))
      (node (ref "R7") (pin "1") (pinfunction "1_1") (pintype "passive"))
    )
    (net (code "44") (name "Net-(I2C_PU-Pad1)") (class "Default")
      (node (ref "I2C_PU") (pin "1") (pinfunction "1_1") (pintype "passive"))
      (node (ref "R15") (pin "2") (pinfunction "2_2") (pintype "passive"))
    )
    (net (code "45") (name "Net-(I2C_PU-Pad3)") (class "Default")
      (node (ref "I2C_PU") (pin "3") (pinfunction "3_3") (pintype "passive"))
      (node (ref "R14") (pin "2") (pinfunction "2_2") (pintype "passive"))
    )
    (net (code "46") (name "Net-(J3-CC1)") (class "Default")
      (node (ref "J3") (pin "A5") (pinfunction "CC1_A5") (pintype "bidirectional"))
      (node (ref "R1") (pin "2") (pinfunction "2_2") (pintype "passive"))
    )
    (net (code "47") (name "Net-(J3-CC2)") (class "Default")
      (node (ref "J3") (pin "B5") (pinfunction "CC2_B5") (pintype "bidirectional"))
      (node (ref "R2") (pin "2") (pinfunction "2_2") (pintype "passive"))
    )
    (net (code "48") (name "Net-(J3-SHLD-PadSHLD1)") (class "Default")
      (node (ref "J3") (pin "SHLD1") (pinfunction "SHLD_SHLD1") (pintype "bidirectional"))
      (node (ref "J3") (pin "SHLD2") (pinfunction "SHLD_SHLD2") (pintype "bidirectional"))
      (node (ref "J3") (pin "SHLD3") (pinfunction "SHLD_SHLD3") (pintype "bidirectional"))
      (node (ref "J3") (pin "SHLD4") (pinfunction "SHLD_SHLD4") (pintype "bidirectional"))
      (node (ref "SHLD") (pin "2") (pinfunction "2_2") (pintype "passive"))
    )
    (net (code "49") (name "Net-(J10-VCC)") (class "Default")
      (node (ref "C7") (pin "2") (pinfunction "2_2") (pintype "passive"))
      (node (ref "J10") (pin "4") (pinfunction "VCC_4") (pintype "bidirectional"))
      (node (ref "Q2") (pin "3") (pinfunction "D_3") (pintype "bidirectional"))
    )
    (net (code "50") (name "Net-(Q2-G)") (class "Default")
      (node (ref "Q2") (pin "1") (pinfunction "G_1") (pintype "bidirectional"))
      (node (ref "R18") (pin "2") (pinfunction "2_2") (pintype "passive"))
      (node (ref "R19") (pin "1") (pinfunction "1_1") (pintype "passive"))
    )
    (net (code "51") (name "Net-(U2-PROG)") (class "Default")
      (node (ref "R3") (pin "2") (pinfunction "2_2") (pintype "passive"))
      (node (ref "U2") (pin "5") (pinfunction "PROG_5") (pintype "input"))
    )
    (net (code "52") (name "Net-(U2-STAT)") (class "Default")
      (node (ref "D4") (pin "C") (pinfunction "C_C") (pintype "passive"))
      (node (ref "U2") (pin "1") (pinfunction "STAT_1") (pintype "output"))
    )
    (net (code "53") (name "Net-(U5-EN)") (class "Default")
      (node (ref "D1") (pin "C") (pinfunction "C_C") (pintype "passive"))
      (node (ref "R9") (pin "1") (pinfunction "1_1") (pintype "passive"))
      (node (ref "U5") (pin "5") (pinfunction "EN_5") (pintype "bidirectional"))
      (node (ref "VE") (pin "2") (pinfunction "2_2") (pintype "passive"))
    )
    (net (code "54") (name "Net-(U5-IN)") (class "Default")
      (node (ref "5V_MEAS") (pin "2") (pinfunction "2_2") (pintype "passive"))
      (node (ref "5V_MEAS") (pin "4") (pinfunction "2_4") (pintype "passive"))
      (node (ref "C5") (pin "1") (pinfunction "1_1") (pintype "passive"))
      (node (ref "C8") (pin "1") (pinfunction "1_1") (pintype "passive"))
      (node (ref "R9") (pin "2") (pinfunction "2_2") (pintype "passive"))
      (node (ref "U5") (pin "8") (pinfunction "IN_8") (pintype "input"))
    )
    (net (code "55") (name "Net-(U5-OUT)") (class "Default")
      (node (ref "3V3_MEAS") (pin "1") (pinfunction "1_1") (pintype "passive"))
      (node (ref "3V3_MEAS") (pin "3") (pinfunction "1_3") (pintype "passive"))
      (node (ref "C11") (pin "1") (pinfunction "1_1") (pintype "passive"))
      (node (ref "C6") (pin "1") (pinfunction "1_1") (pintype "passive"))
      (node (ref "R17") (pin "2") (pinfunction "2_2") (pintype "passive"))
      (node (ref "U5") (pin "1") (pinfunction "OUT_1") (pintype "output"))
    )
    (net (code "56") (name "PROCESSOR_CAN-RX") (class "Default")
      (node (ref "J1") (pin "41") (pinfunction "CAN-RX_41") (pintype "bidirectional"))
      (node (ref "J6") (pin "43") (pinfunction "CAN-TX_43") (pintype "bidirectional"))
    )
    (net (code "57") (name "PROCESSOR_CAN-TX") (class "Default")
      (node (ref "J1") (pin "43") (pinfunction "CAN-TX_43") (pintype "bidirectional"))
      (node (ref "J6") (pin "41") (pinfunction "CAN-RX_41") (pintype "bidirectional"))
    )
    (net (code "58") (name "PWM0-PROCESSOR") (class "Default")
      (node (ref "J1") (pin "32") (pinfunction "PWM0_32") (pintype "bidirectional"))
      (node (ref "J6") (pin "51") (pinfunction "F2/PWM_51") (pintype "bidirectional"))
    )
    (net (code "59") (name "PWM1-PROCESSOR") (class "Default")
      (node (ref "J1") (pin "47") (pinfunction "PWM1_47") (pintype "bidirectional"))
      (node (ref "J7") (pin "51") (pinfunction "F2/PWM_51") (pintype "bidirectional"))
    )
    (net (code "60") (name "RTS1-PROCESSOR") (class "Default")
      (node (ref "J1") (pin "13") (pinfunction "RTS1_13") (pintype "bidirectional"))
      (node (ref "J6") (pin "18") (pinfunction "CTS_18") (pintype "bidirectional"))
    )
    (net (code "61") (name "RX1-DFU_TX-FC0-PLEX") (class "Default")
      (node (ref "J6") (pin "4") (pinfunction "MCU_DFU_TX_4") (pintype "bidirectional"))
      (node (ref "U1") (pin "P9") (pinfunction "2S1_P9") (pintype "bidirectional"))
    )
    (net (code "62") (name "RX1-DFU_TX-FC1-PLEX") (class "Default")
      (node (ref "J7") (pin "4") (pinfunction "MCU_DFU_TX_4") (pintype "bidirectional"))
      (node (ref "U1") (pin "P8") (pinfunction "2S2_P8") (pintype "bidirectional"))
    )
    (net (code "63") (name "RX1-PROCESSOR") (class "Default")
      (node (ref "J1") (pin "19") (pinfunction "RX1_19") (pintype "bidirectional"))
      (node (ref "U1") (pin "P6") (pinfunction "D2_P6") (pintype "bidirectional"))
    )
    (net (code "64") (name "RX1-PROCESSOR-PLEX") (class "Default")
      (node (ref "J6") (pin "13") (pinfunction "TX_13") (pintype "bidirectional"))
      (node (ref "U1") (pin "P7") (pinfunction "2S3_P7") (pintype "bidirectional"))
    )
    (net (code "65") (name "RX2-PROCESSOR") (class "Default")
      (node (ref "J1") (pin "20") (pinfunction "RX2_20") (pintype "bidirectional"))
      (node (ref "J7") (pin "13") (pinfunction "TX_13") (pintype "bidirectional"))
    )
    (net (code "66") (name "SDIO_DATA1{slash}PWR_EN1_ALT") (class "Default")
      (node (ref "J1") (pin "66") (pinfunction "SDIO_DATA1_66") (pintype "bidirectional"))
      (node (ref "J7") (pin "71") (pinfunction "PWR_EN_71") (pintype "bidirectional"))
      (node (ref "S7") (pin "3") (pinfunction "S_3") (pintype "passive"))
    )
    (net (code "67") (name "SDIO_DATA2{slash}PWR_EN0_ALT") (class "Default")
      (node (ref "J1") (pin "68") (pinfunction "SDIO_DATA2_68") (pintype "bidirectional"))
      (node (ref "J6") (pin "71") (pinfunction "PWR_EN_71") (pintype "bidirectional"))
      (node (ref "S3") (pin "3") (pinfunction "S_3") (pintype "passive"))
    )
    (net (code "68") (name "SPI_PROCESSOR_SCK") (class "Default")
      (node (ref "J1") (pin "57") (pinfunction "SPI_SCK_57") (pintype "bidirectional"))
      (node (ref "J10") (pin "5") (pinfunction "CLK/SCK_5") (pintype "bidirectional"))
      (node (ref "J6") (pin "3") (pinfunction "SPI_SCK_3") (pintype "bidirectional"))
      (node (ref "J7") (pin "3") (pinfunction "SPI_SCK_3") (pintype "bidirectional"))
    )
    (net (code "69") (name "SPI_PROCESSOR_SDI") (class "Default")
      (node (ref "J1") (pin "61") (pinfunction "SPI_SDI_61") (pintype "bidirectional"))
      (node (ref "J10") (pin "7") (pinfunction "DAT0/SDO_7") (pintype "bidirectional"))
      (node (ref "J6") (pin "7") (pinfunction "SPI_SDO_7") (pintype "bidirectional"))
      (node (ref "J7") (pin "7") (pinfunction "SPI_SDO_7") (pintype "bidirectional"))
    )
    (net (code "70") (name "SPI_PROCESSOR_SDO") (class "Default")
      (node (ref "J1") (pin "59") (pinfunction "SPI_SDO_59") (pintype "bidirectional"))
      (node (ref "J10") (pin "3") (pinfunction "CMD/SDI_3") (pintype "bidirectional"))
      (node (ref "J6") (pin "5") (pinfunction "SPI_SDI_5") (pintype "bidirectional"))
      (node (ref "J7") (pin "5") (pinfunction "SPI_SDI_5") (pintype "bidirectional"))
    )
    (net (code "71") (name "SPI_SCK1-PROCESSOR") (class "Default")
      (node (ref "J1") (pin "60") (pinfunction "SPI_SCK1/SDIO_CLK_60") (pintype "bidirectional"))
      (node (ref "J7") (pin "61") (pinfunction "F7_61") (pintype "bidirectional"))
    )
    (net (code "72") (name "SPI_SDO1-PROCESSOR") (class "Default")
      (node (ref "J1") (pin "62") (pinfunction "SPI_SDO1/SDIO_CMD_62") (pintype "bidirectional"))
      (node (ref "J7") (pin "59") (pinfunction "F6_59") (pintype "bidirectional"))
    )
    (net (code "73") (name "SWDCK") (class "Default")
      (node (ref "J1") (pin "21") (pinfunction "SWDCK_21") (pintype "bidirectional"))
      (node (ref "J5") (pin "4") (pinfunction "SWDCLK_4") (pintype "bidirectional"))
    )
    (net (code "74") (name "SWDIO") (class "Default")
      (node (ref "J1") (pin "23") (pinfunction "SWDIO_23") (pintype "bidirectional"))
      (node (ref "J5") (pin "2") (pinfunction "SWDIO_2") (pintype "bidirectional"))
      (node (ref "TP1") (pin "1") (pinfunction "1_1") (pintype "bidirectional"))
    )
    (net (code "75") (name "TX1-DFU_RX-FC0-PLEX") (class "Default")
      (node (ref "J6") (pin "6") (pinfunction "MCU_DFU_RX_6") (pintype "bidirectional"))
      (node (ref "U1") (pin "P1") (pinfunction "1S1_P1") (pintype "bidirectional"))
    )
    (net (code "76") (name "TX1-DFU_RX-FC1-PLEX") (class "Default")
      (node (ref "J7") (pin "6") (pinfunction "MCU_DFU_RX_6") (pintype "bidirectional"))
      (node (ref "U1") (pin "P2") (pinfunction "1S2_P2") (pintype "bidirectional"))
    )
    (net (code "77") (name "TX1-PROCESSOR") (class "Default")
      (node (ref "J1") (pin "17") (pinfunction "TX1_17") (pintype "bidirectional"))
      (node (ref "U1") (pin "P4") (pinfunction "D1_P4") (pintype "bidirectional"))
    )
    (net (code "78") (name "TX1-PROCESSOR-PLEX") (class "Default")
      (node (ref "J6") (pin "15") (pinfunction "RX_15") (pintype "bidirectional"))
      (node (ref "U1") (pin "P3") (pinfunction "1S3_P3") (pintype "bidirectional"))
    )
    (net (code "79") (name "TX2-PROCESSOR") (class "Default")
      (node (ref "J1") (pin "22") (pinfunction "TX2_22") (pintype "bidirectional"))
      (node (ref "J7") (pin "15") (pinfunction "RX_15") (pintype "bidirectional"))
    )
    (net (code "80") (name "VCC") (class "Default")
      (node (ref "5V_MEAS") (pin "1") (pinfunction "1_1") (pintype "passive"))
      (node (ref "5V_MEAS") (pin "3") (pinfunction "1_3") (pintype "passive"))
      (node (ref "C2") (pin "1") (pinfunction "1_1") (pintype "passive"))
      (node (ref "C3") (pin "1") (pinfunction "1_1") (pintype "passive"))
      (node (ref "D5") (pin "C") (pinfunction "C_C") (pintype "passive"))
      (node (ref "J6") (pin "72") (pinfunction "VCC_72") (pintype "bidirectional"))
      (node (ref "J6") (pin "74") (pinfunction "VCC_74") (pintype "bidirectional"))
      (node (ref "J7") (pin "72") (pinfunction "VCC_72") (pintype "bidirectional"))
      (node (ref "J7") (pin "74") (pinfunction "VCC_74") (pintype "bidirectional"))
      (node (ref "Q1") (pin "2") (pinfunction "S_2") (pintype "bidirectional"))
      (node (ref "R4") (pin "2") (pinfunction "2_2") (pintype "passive"))
      (node (ref "R5") (pin "1") (pinfunction "1_1") (pintype "passive"))
      (node (ref "U2") (pin "4") (pinfunction "VIN_4") (pintype "power_in"))
      (node (ref "U4") (pin "1") (pinfunction "IN_1") (pintype "input"))
    )
    (net (code "81") (name "VIN") (class "Default")
      (node (ref "BYP") (pin "2") (pinfunction "2_2") (pintype "passive"))
      (node (ref "D5") (pin "A") (pinfunction "A_A") (pintype "passive"))
      (node (ref "F2") (pin "2") (pinfunction "2_2") (pintype "bidirectional"))
      (node (ref "J1") (pin "9") (pinfunction "USB_VIN_9") (pintype "bidirectional"))
      (node (ref "Q1") (pin "1") (pinfunction "G_1") (pintype "bidirectional"))
      (node (ref "R10") (pin "2") (pinfunction "2_2") (pintype "passive"))
      (node (ref "R6") (pin "2") (pinfunction "2_2") (pintype "passive"))
      (node (ref "R8") (pin "2") (pinfunction "2_2") (pintype "passive"))
      (node (ref "TP4") (pin "1") (pinfunction "1_1") (pintype "bidirectional"))
    )
    (net (code "82") (name "VIN{slash}3") (class "Default")
      (node (ref "J1") (pin "49") (pinfunction "BATT_VIN/3_49") (pintype "bidirectional"))
      (node (ref "R10") (pin "1") (pinfunction "1_1") (pintype "passive"))
      (node (ref "R7") (pin "2") (pinfunction "2_2") (pintype "passive"))
    )
    (net (code "83") (name "V_BATT") (class "Default")
      (node (ref "C4") (pin "1") (pinfunction "1_1") (pintype "passive"))
      (node (ref "J11") (pin "2") (pinfunction "2_2") (pintype "passive"))
      (node (ref "J8") (pin "2") (pinfunction "+_2") (pintype "bidirectional"))
      (node (ref "Q1") (pin "3") (pinfunction "D_3") (pintype "bidirectional"))
      (node (ref "TP3") (pin "1") (pinfunction "1_1") (pintype "bidirectional"))
      (node (ref "U2") (pin "3") (pinfunction "VBAT_3") (pintype "power_in"))
    )
    (net (code "84") (name "V_USB") (class "Default")
      (node (ref "BYP") (pin "1") (pinfunction "1_1") (pintype "passive"))
      (node (ref "F2") (pin "1") (pinfunction "1_1") (pintype "bidirectional"))
      (node (ref "J3") (pin "VBUS1") (pinfunction "VBUS_VBUS1") (pintype "bidirectional"))
      (node (ref "J3") (pin "VBUS2") (pinfunction "VBUS_VBUS2") (pintype "bidirectional"))
      (node (ref "U3") (pin "5") (pinfunction "VCC_5") (pintype "bidirectional"))
    )
    (net (code "85") (name "unconnected-(J1-AUD_BCLK-Pad50)") (class "Default")
      (node (ref "J1") (pin "50") (pinfunction "AUD_BCLK_50") (pintype "bidirectional"))
    )
    (net (code "86") (name "unconnected-(J1-AUD_IN{slash}CAM_PCLK-Pad54)") (class "Default")
      (node (ref "J1") (pin "54") (pinfunction "AUD_IN/CAM_PCLK_54") (pintype "bidirectional"))
    )
    (net (code "87") (name "unconnected-(J1-AUD_LRCLK-Pad52)") (class "Default")
      (node (ref "J1") (pin "52") (pinfunction "AUD_LRCLK_52") (pintype "bidirectional"))
    )
    (net (code "88") (name "unconnected-(J1-AUD_MCLK-Pad58)") (class "Default")
      (node (ref "J1") (pin "58") (pinfunction "AUD_MCLK_58") (pintype "bidirectional"))
    )
    (net (code "89") (name "unconnected-(J1-AUD_OUT{slash}CAM_MCLK-Pad56)") (class "Default")
      (node (ref "J1") (pin "56") (pinfunction "AUD_OUT/CAM_MCLK_56") (pintype "bidirectional"))
    )
    (net (code "90") (name "unconnected-(J1-G8-Pad67)") (class "Default")
      (node (ref "J1") (pin "67") (pinfunction "G8_67") (pintype "bidirectional"))
    )
    (net (code "91") (name "unconnected-(J1-G9{slash}ADC_D-{slash}CAM_HSYNC-Pad65)") (class "Default")
      (node (ref "J1") (pin "65") (pinfunction "G9/ADC_D-/CAM_HSYNC_65") (pintype "bidirectional"))
    )
    (net (code "92") (name "unconnected-(J1-G10{slash}ADC_D+{slash}CAM_VSYNC-Pad63)") (class "Default")
      (node (ref "J1") (pin "63") (pinfunction "G10/ADC_D+/CAM_VSYNC_63") (pintype "bidirectional"))
    )
    (net (code "93") (name "unconnected-(J1-G11-Pad8)") (class "Default")
      (node (ref "J1") (pin "8") (pinfunction "G11_8") (pintype "bidirectional"))
    )
    (net (code "94") (name "unconnected-(J1-RTC_3V-Pad72)") (class "Default")
      (node (ref "J1") (pin "72") (pinfunction "RTC_3V_72") (pintype "bidirectional"))
    )
    (net (code "95") (name "unconnected-(J1-SPI_SDI1{slash}SDIO_DATA0-Pad64)") (class "Default")
      (node (ref "J1") (pin "64") (pinfunction "SPI_SDI1/SDIO_DATA0_64") (pintype "bidirectional"))
    )
    (net (code "96") (name "unconnected-(J5-SWO-Pad6)") (class "Default")
      (node (ref "J5") (pin "6") (pinfunction "SWO_6") (pintype "bidirectional"))
    )
    (net (code "97") (name "unconnected-(J6-EEPROM_WP-Pad40)") (class "Default")
      (node (ref "J6") (pin "40") (pinfunction "EEPROM_WP_40") (pintype "bidirectional"))
    )
    (net (code "98") (name "unconnected-(J6-USB_VIN-Pad70)") (class "Default")
      (node (ref "J6") (pin "70") (pinfunction "USB_VIN_70") (pintype "bidirectional"))
    )
    (net (code "99") (name "unconnected-(J7-CAN-RX-Pad41)") (class "Default")
      (node (ref "J7") (pin "41") (pinfunction "CAN-RX_41") (pintype "bidirectional"))
    )
    (net (code "100") (name "unconnected-(J7-CAN-TX-Pad43)") (class "Default")
      (node (ref "J7") (pin "43") (pinfunction "CAN-TX_43") (pintype "bidirectional"))
    )
    (net (code "101") (name "unconnected-(J7-CTS-Pad18)") (class "Default")
      (node (ref "J7") (pin "18") (pinfunction "CTS_18") (pintype "bidirectional"))
    )
    (net (code "102") (name "unconnected-(J7-EEPROM_WP-Pad40)") (class "Default")
      (node (ref "J7") (pin "40") (pinfunction "EEPROM_WP_40") (pintype "bidirectional"))
    )
    (net (code "103") (name "unconnected-(J7-RTS-Pad16)") (class "Default")
      (node (ref "J7") (pin "16") (pinfunction "RTS_16") (pintype "bidirectional"))
    )
    (net (code "104") (name "unconnected-(J7-USBHOST_D+-Pad35)") (class "Default")
      (node (ref "J7") (pin "35") (pinfunction "USBHOST_D+_35") (pintype "bidirectional"))
    )
    (net (code "105") (name "unconnected-(J7-USBHOST_D--Pad37)") (class "Default")
      (node (ref "J7") (pin "37") (pinfunction "USBHOST_D-_37") (pintype "bidirectional"))
    )
    (net (code "106") (name "unconnected-(J7-USB_VIN-Pad70)") (class "Default")
      (node (ref "J7") (pin "70") (pinfunction "USB_VIN_70") (pintype "bidirectional"))
    )
    (net (code "107") (name "unconnected-(J8-PAD1-PadNC1)") (class "Default")
      (node (ref "J8") (pin "NC1") (pinfunction "PAD1_NC1") (pintype "bidirectional"))
    )
    (net (code "108") (name "unconnected-(J8-PAD2-PadNC2)") (class "Default")
      (node (ref "J8") (pin "NC2") (pinfunction "PAD2_NC2") (pintype "bidirectional"))
    )
    (net (code "109") (name "unconnected-(J10-DAT1-Pad8)") (class "Default")
      (node (ref "J10") (pin "8") (pinfunction "DAT1_8") (pintype "bidirectional"))
    )
    (net (code "110") (name "unconnected-(J10-DAT2-Pad1)") (class "Default")
      (node (ref "J10") (pin "1") (pinfunction "DAT2_1") (pintype "bidirectional"))
    )
    (net (code "111") (name "unconnected-(J10-DET-Pad9)") (class "Default")
      (node (ref "J10") (pin "9") (pinfunction "DET_9") (pintype "bidirectional"))
    )
    (net (code "112") (name "unconnected-(U3-IO1-Pad1)") (class "Default")
      (node (ref "U3") (pin "1") (pinfunction "IO1_1") (pintype "bidirectional"))
    )
    (net (code "113") (name "unconnected-(U3-IO2-Pad3)") (class "Default")
      (node (ref "U3") (pin "3") (pinfunction "IO2_3") (pintype "bidirectional"))
    )
  )
)
